# nfc_edit.net
KiCad netlist of a schematic drawn in EAGLE
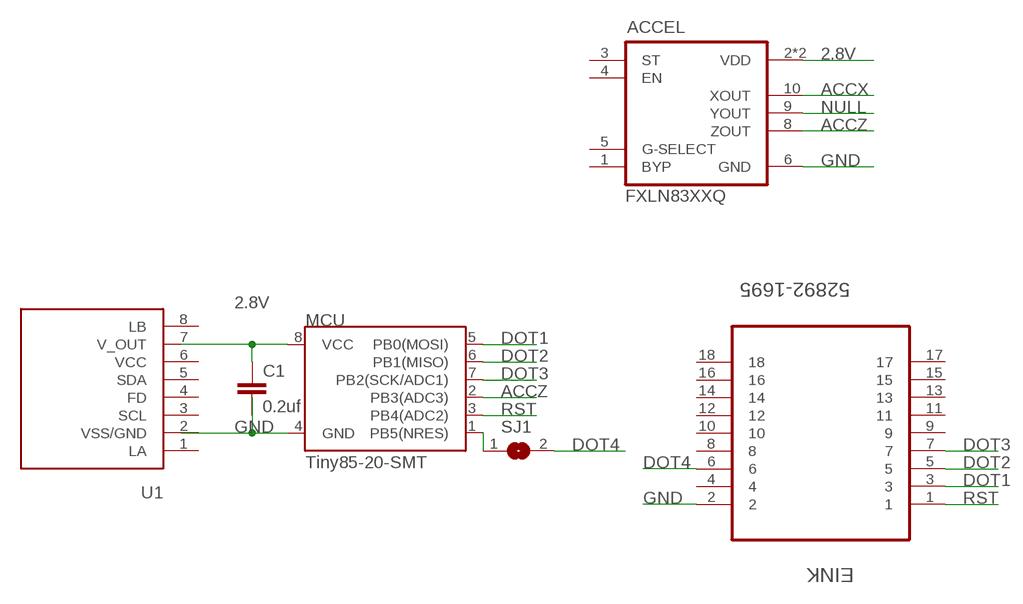
[diagram p0: schematic, sheet 1]

(export (version "E")
  (design (tool "Eeschema 10.0.6"))
  (components
    (comp (ref "ACCEL")
      (value "FXLN83XXQ")
      (footprint "eagle-import:QFN12-3X3")
      (libsource (lib "eagle-import") (part "FXLN83XXQ"))
    )
    (comp (ref "C1")
      (value "0.2uf")
      (footprint "eagle-import:1206")
      (libsource (lib "eagle-import") (part "CAP1206"))
    )
    (comp (ref "EINK")
      (value "52892-1695")
      (footprint "eagle-import:MOLEX_52892-1695")
      (libsource (lib "eagle-import") (part "52892-1695"))
    )
    (comp (ref "MCU")
      (value "Tiny85-20-SMT")
      (footprint "eagle-import:SO08-EIAJ")
      (libsource (lib "eagle-import") (part "ATTINY45TINY85-20-SMT"))
    )
    (comp (ref "SJ1")
      (value "SOLDERJUMPER")
      (footprint "eagle-import:SOLDERJUMPER_ARROW_NOPASTE")
      (libsource (lib "eagle-import") (part "SOLDERJUMPER"))
    )
    (comp (ref "U1")
      (value "NT3H1101")
      (footprint "eagle-import:NT3H1101")
      (libsource (lib "eagle-import") (part "NT3H1101"))
    )
  )
  (nets
    (net (code "1") (name "/2.8V") (class "Default")
      (node (ref "ACCEL") (pin "2") (pinfunction "VDD_2") (pintype "power_in"))
      (node (ref "ACCEL") (pin "7") (pinfunction "VDD_7") (pintype "power_in"))
      (node (ref "C1") (pin "1") (pinfunction "1_1") (pintype "passive"))
      (node (ref "MCU") (pin "8") (pinfunction "VCC_8") (pintype "bidirectional"))
      (node (ref "U1") (pin "7") (pinfunction "V_OUT_7") (pintype "power_in"))
    )
    (net (code "2") (name "/ACCX") (class "Default")
      (node (ref "ACCEL") (pin "10") (pinfunction "XOUT_10") (pintype "output"))
    )
    (net (code "3") (name "/ACCZ") (class "Default")
      (node (ref "ACCEL") (pin "8") (pinfunction "ZOUT_8") (pintype "output"))
      (node (ref "MCU") (pin "2") (pinfunction "PB3(ADC3)_2") (pintype "bidirectional"))
    )
    (net (code "4") (name "/DOT1") (class "Default")
      (node (ref "EINK") (pin "3") (pinfunction "3_3") (pintype "passive"))
      (node (ref "MCU") (pin "5") (pinfunction "PB0(MOSI)_5") (pintype "bidirectional"))
    )
    (net (code "5") (name "/DOT2") (class "Default")
      (node (ref "EINK") (pin "5") (pinfunction "5_5") (pintype "passive"))
      (node (ref "MCU") (pin "6") (pinfunction "PB1(MISO)_6") (pintype "bidirectional"))
    )
    (net (code "6") (name "/DOT3") (class "Default")
      (node (ref "EINK") (pin "7") (pinfunction "7_7") (pintype "passive"))
      (node (ref "MCU") (pin "7") (pinfunction "PB2(SCK/ADC1)_7") (pintype "bidirectional"))
    )
    (net (code "7") (name "/DOT4") (class "Default")
      (node (ref "EINK") (pin "6") (pinfunction "6_6") (pintype "passive"))
      (node (ref "SJ1") (pin "2") (pinfunction "2_2") (pintype "passive"))
    )
    (net (code "8") (name "/GND") (class "Default")
      (node (ref "ACCEL") (pin "6") (pinfunction "GND_6") (pintype "power_in"))
      (node (ref "EINK") (pin "2") (pinfunction "2_2") (pintype "passive"))
      (node (ref "MCU") (pin "4") (pinfunction "GND_4") (pintype "bidirectional"))
    )
    (net (code "9") (name "/NULL") (class "Default")
      (node (ref "ACCEL") (pin "9") (pinfunction "YOUT_9") (pintype "output"))
    )
    (net (code "10") (name "/RST") (class "Default")
      (node (ref "EINK") (pin "1") (pinfunction "1_1") (pintype "passive"))
      (node (ref "MCU") (pin "3") (pinfunction "PB4(ADC2)_3") (pintype "bidirectional"))
    )
    (net (code "11") (name "/VCC") (class "Default")
      (node (ref "U1") (pin "6") (pinfunction "VCC_6") (pintype "power_in"))
    )
    (net (code "12") (name "/VSS{slash}GND") (class "Default")
      (node (ref "U1") (pin "2") (pinfunction "VSS/GND_2") (pintype "power_in"))
    )
    (net (code "13") (name "Net-(MCU-PB5(NRES))") (class "Default")
      (node (ref "MCU") (pin "1") (pinfunction "PB5(NRES)_1") (pintype "bidirectional"))
      (node (ref "SJ1") (pin "1") (pinfunction "1_1") (pintype "passive"))
    )
    (net (code "14") (name "unconnected-(ACCEL-BYP-Pad1)") (class "Default")
      (node (ref "ACCEL") (pin "1") (pinfunction "BYP_1") (pintype "bidirectional"))
    )
    (net (code "15") (name "unconnected-(ACCEL-EN-Pad4)") (class "Default")
      (node (ref "ACCEL") (pin "4") (pinfunction "EN_4") (pintype "bidirectional"))
    )
    (net (code "16") (name "unconnected-(ACCEL-G-SELECT-Pad5)") (class "Default")
      (node (ref "ACCEL") (pin "5") (pinfunction "G-SELECT_5") (pintype "bidirectional"))
    )
    (net (code "17") (name "unconnected-(ACCEL-ST-Pad3)") (class "Default")
      (node (ref "ACCEL") (pin "3") (pinfunction "ST_3") (pintype "bidirectional"))
    )
    (net (code "18") (name "unconnected-(C1-Pad2)") (class "Default")
      (node (ref "C1") (pin "2") (pinfunction "2_2") (pintype "passive"))
    )
    (net (code "19") (name "unconnected-(EINK-Pad4)") (class "Default")
      (node (ref "EINK") (pin "4") (pinfunction "4_4") (pintype "passive"))
    )
    (net (code "20") (name "unconnected-(EINK-Pad8)") (class "Default")
      (node (ref "EINK") (pin "8") (pinfunction "8_8") (pintype "passive"))
    )
    (net (code "21") (name "unconnected-(EINK-Pad9)") (class "Default")
      (node (ref "EINK") (pin "9") (pinfunction "9_9") (pintype "passive"))
    )
    (net (code "22") (name "unconnected-(EINK-Pad10)") (class "Default")
      (node (ref "EINK") (pin "10") (pinfunction "10_10") (pintype "passive"))
    )
    (net (code "23") (name "unconnected-(EINK-Pad11)") (class "Default")
      (node (ref "EINK") (pin "11") (pinfunction "11_11") (pintype "passive"))
    )
    (net (code "24") (name "unconnected-(EINK-Pad12)") (class "Default")
      (node (ref "EINK") (pin "12") (pinfunction "12_12") (pintype "passive"))
    )
    (net (code "25") (name "unconnected-(EINK-Pad13)") (class "Default")
      (node (ref "EINK") (pin "13") (pinfunction "13_13") (pintype "passive"))
    )
    (net (code "26") (name "unconnected-(EINK-Pad14)") (class "Default")
      (node (ref "EINK") (pin "14") (pinfunction "14_14") (pintype "passive"))
    )
    (net (code "27") (name "unconnected-(EINK-Pad15)") (class "Default")
      (node (ref "EINK") (pin "15") (pinfunction "15_15") (pintype "passive"))
    )
    (net (code "28") (name "unconnected-(EINK-Pad16)") (class "Default")
      (node (ref "EINK") (pin "16") (pinfunction "16_16") (pintype "passive"))
    )
    (net (code "29") (name "unconnected-(EINK-Pad17)") (class "Default")
      (node (ref "EINK") (pin "17") (pinfunction "17_17") (pintype "passive"))
    )
    (net (code "30") (name "unconnected-(EINK-Pad18)") (class "Default")
      (node (ref "EINK") (pin "18") (pinfunction "18_18") (pintype "passive"))
    )
    (net (code "31") (name "unconnected-(U1-FD-Pad4)") (class "Default")
      (node (ref "U1") (pin "4") (pinfunction "FD_4") (pintype "bidirectional"))
    )
    (net (code "32") (name "unconnected-(U1-LA-Pad1)") (class "Default")
      (node (ref "U1") (pin "1") (pinfunction "LA_1") (pintype "bidirectional"))
    )
    (net (code "33") (name "unconnected-(U1-LB-Pad8)") (class "Default")
      (node (ref "U1") (pin "8") (pinfunction "LB_8") (pintype "bidirectional"))
    )
    (net (code "34") (name "unconnected-(U1-SCL-Pad3)") (class "Default")
      (node (ref "U1") (pin "3") (pinfunction "SCL_3") (pintype "bidirectional"))
    )
    (net (code "35") (name "unconnected-(U1-SDA-Pad5)") (class "Default")
      (node (ref "U1") (pin "5") (pinfunction "SDA_5") (pintype "bidirectional"))
    )
  )
)
